# 04_Motor_Driver.net
KiCad netlist of a schematic drawn in Altium Designer
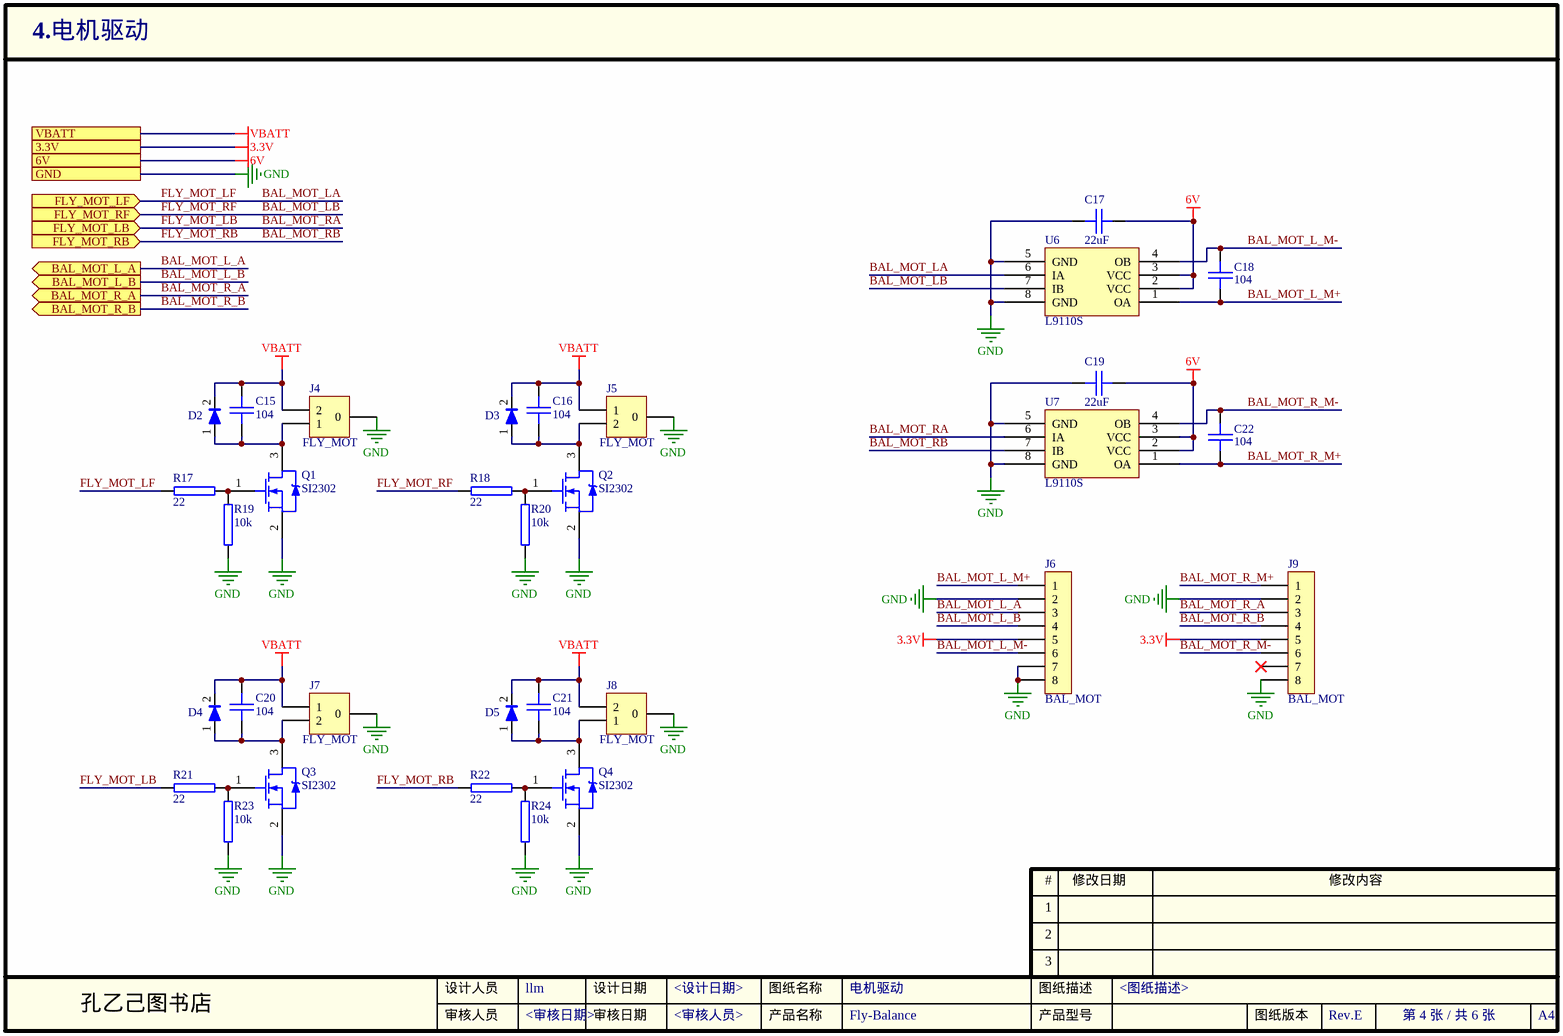
[diagram p0: 04_Motor_Driver.SchDoc]

(export (version "E")
  (design (tool "Eeschema 10.0.6"))
  (components
    (comp (ref "C15")
      (value "104")
      (footprint "0402C")
      (description "电容")
      (libsource (lib "MY_Schlib") (part "CAP"))
    )
    (comp (ref "C16")
      (value "104")
      (footprint "0402C")
      (description "电容")
      (libsource (lib "MY_Schlib") (part "CAP"))
    )
    (comp (ref "C17")
      (value "22uF")
      (footprint "0805C")
      (description "电容")
      (libsource (lib "MY_Schlib") (part "CAP"))
    )
    (comp (ref "C18")
      (value "104")
      (footprint "0402C")
      (description "电容")
      (libsource (lib "MY_Schlib") (part "CAP"))
    )
    (comp (ref "C19")
      (value "22uF")
      (footprint "0805C")
      (description "电容")
      (libsource (lib "MY_Schlib") (part "CAP"))
    )
    (comp (ref "C20")
      (value "104")
      (footprint "0402C")
      (description "电容")
      (libsource (lib "MY_Schlib") (part "CAP"))
    )
    (comp (ref "C21")
      (value "104")
      (footprint "0402C")
      (description "电容")
      (libsource (lib "MY_Schlib") (part "CAP"))
    )
    (comp (ref "C22")
      (value "104")
      (footprint "0402C")
      (description "电容")
      (libsource (lib "MY_Schlib") (part "CAP"))
    )
    (comp (ref "D2")
      (value "1N4001")
      (footprint "SOD-323")
      (description "二极管")
      (libsource (lib "MY_Schlib") (part "DIODE"))
    )
    (comp (ref "D3")
      (value "1N4001")
      (footprint "SOD-323")
      (description "二极管")
      (libsource (lib "MY_Schlib") (part "DIODE"))
    )
    (comp (ref "D4")
      (value "1N4001")
      (footprint "SOD-323")
      (description "二极管")
      (libsource (lib "MY_Schlib") (part "DIODE"))
    )
    (comp (ref "D5")
      (value "1N4001")
      (footprint "SOD-323")
      (description "二极管")
      (libsource (lib "MY_Schlib") (part "DIODE"))
    )
    (comp (ref "J4")
      (value "FLY_MOT")
      (footprint "CONN-SMD_2P-P1.25")
      (description "直流电机接口")
      (libsource (lib "Schlib") (part "CON"))
    )
    (comp (ref "J5")
      (value "FLY_MOT")
      (footprint "CONN-SMD_2P-P1.25")
      (description "直流电机接口")
      (libsource (lib "") (part "CON_1"))
    )
    (comp (ref "J6")
      (value "BAL_MOT")
      (footprint "CONN-SMD_6P-P2.00_DEALON_PH-6PWB")
      (description "Connector")
      (libsource (lib "MY_Schlib") (part "CON8"))
    )
    (comp (ref "J7")
      (value "FLY_MOT")
      (footprint "CONN-SMD_2P-P1.25")
      (description "直流电机接口")
      (libsource (lib "") (part "CON_1"))
    )
    (comp (ref "J8")
      (value "FLY_MOT")
      (footprint "CONN-SMD_2P-P1.25")
      (description "直流电机接口")
      (libsource (lib "Schlib") (part "CON"))
    )
    (comp (ref "J9")
      (value "BAL_MOT")
      (footprint "CONN-SMD_6P-P2.00_DEALON_PH-6PWB")
      (description "Connector")
      (libsource (lib "MY_Schlib") (part "CON8"))
    )
    (comp (ref "Q1")
      (value "SI2302")
      (footprint "SOT-23")
      (description "N-MOSFET")
      (libsource (lib "MY_Schlib") (part "N-MOS"))
    )
    (comp (ref "Q2")
      (value "SI2302")
      (footprint "SOT-23")
      (description "N-MOSFET")
      (libsource (lib "MY_Schlib") (part "N-MOS"))
    )
    (comp (ref "Q3")
      (value "SI2302")
      (footprint "SOT-23")
      (description "N-MOSFET")
      (libsource (lib "MY_Schlib") (part "N-MOS"))
    )
    (comp (ref "Q4")
      (value "SI2302")
      (footprint "SOT-23")
      (description "N-MOSFET")
      (libsource (lib "MY_Schlib") (part "N-MOS"))
    )
    (comp (ref "R17")
      (value "22")
      (footprint "0402R")
      (description "电阻")
      (libsource (lib "MY_Schlib") (part "RES"))
    )
    (comp (ref "R18")
      (value "22")
      (footprint "0402R")
      (description "电阻")
      (libsource (lib "MY_Schlib") (part "RES"))
    )
    (comp (ref "R19")
      (value "10k")
      (footprint "0402R")
      (description "电阻")
      (libsource (lib "MY_Schlib") (part "RES"))
    )
    (comp (ref "R20")
      (value "10k")
      (footprint "0402R")
      (description "电阻")
      (libsource (lib "MY_Schlib") (part "RES"))
    )
    (comp (ref "R21")
      (value "22")
      (footprint "0402R")
      (description "电阻")
      (libsource (lib "MY_Schlib") (part "RES"))
    )
    (comp (ref "R22")
      (value "22")
      (footprint "0402R")
      (description "电阻")
      (libsource (lib "MY_Schlib") (part "RES"))
    )
    (comp (ref "R23")
      (value "10k")
      (footprint "0402R")
      (description "电阻")
      (libsource (lib "MY_Schlib") (part "RES"))
    )
    (comp (ref "R24")
      (value "10k")
      (footprint "0402R")
      (description "电阻")
      (libsource (lib "MY_Schlib") (part "RES"))
    )
    (comp (ref "U6")
      (value "L9110S")
      (footprint "SOP-8_L4.9-W3.9-P1.27-LS6.0-BL")
      (description "H桥电机驱动芯片")
      (libsource (lib "MY_Schlib") (part "L9110S"))
    )
    (comp (ref "U7")
      (value "L9110S")
      (footprint "SOP-8_L4.9-W3.9-P1.27-LS6.0-BL")
      (description "H桥电机驱动芯片")
      (libsource (lib "MY_Schlib") (part "L9110S"))
    )
  )
  (nets
    (net (code "1") (name "/BAL_MOT_LA") (class "Default")
      (node (ref "R17") (pin "2") (pinfunction "2_2") (pintype "passive"))
      (node (ref "U6") (pin "6") (pinfunction "IA_6") (pintype "passive"))
    )
    (net (code "2") (name "/BAL_MOT_LB") (class "Default")
      (node (ref "R18") (pin "2") (pinfunction "2_2") (pintype "passive"))
      (node (ref "U6") (pin "7") (pinfunction "IB_7") (pintype "passive"))
    )
    (net (code "3") (name "/BAL_MOT_L_A") (class "Default")
      (node (ref "J6") (pin "3") (pinfunction "3_3") (pintype "passive"))
    )
    (net (code "4") (name "/BAL_MOT_L_B") (class "Default")
      (node (ref "J6") (pin "4") (pinfunction "4_4") (pintype "passive"))
    )
    (net (code "5") (name "/BAL_MOT_L_M+") (class "Default")
      (node (ref "C18") (pin "2") (pinfunction "2_2") (pintype "passive"))
      (node (ref "J6") (pin "1") (pinfunction "1_1") (pintype "passive"))
      (node (ref "U6") (pin "1") (pinfunction "OA_1") (pintype "passive"))
    )
    (net (code "6") (name "/BAL_MOT_L_M-") (class "Default")
      (node (ref "C18") (pin "1") (pinfunction "1_1") (pintype "passive"))
      (node (ref "J6") (pin "6") (pinfunction "6_6") (pintype "passive"))
      (node (ref "U6") (pin "4") (pinfunction "OB_4") (pintype "passive"))
    )
    (net (code "7") (name "/BAL_MOT_RA") (class "Default")
      (node (ref "R21") (pin "2") (pinfunction "2_2") (pintype "passive"))
      (node (ref "U7") (pin "6") (pinfunction "IA_6") (pintype "passive"))
    )
    (net (code "8") (name "/BAL_MOT_RB") (class "Default")
      (node (ref "R22") (pin "2") (pinfunction "2_2") (pintype "passive"))
      (node (ref "U7") (pin "7") (pinfunction "IB_7") (pintype "passive"))
    )
    (net (code "9") (name "/BAL_MOT_R_A") (class "Default")
      (node (ref "J9") (pin "3") (pinfunction "3_3") (pintype "passive"))
    )
    (net (code "10") (name "/BAL_MOT_R_B") (class "Default")
      (node (ref "J9") (pin "4") (pinfunction "4_4") (pintype "passive"))
    )
    (net (code "11") (name "/BAL_MOT_R_M+") (class "Default")
      (node (ref "C22") (pin "2") (pinfunction "2_2") (pintype "passive"))
      (node (ref "J9") (pin "1") (pinfunction "1_1") (pintype "passive"))
      (node (ref "U7") (pin "1") (pinfunction "OA_1") (pintype "passive"))
    )
    (net (code "12") (name "/BAL_MOT_R_M-") (class "Default")
      (node (ref "C22") (pin "1") (pinfunction "1_1") (pintype "passive"))
      (node (ref "J9") (pin "6") (pinfunction "6_6") (pintype "passive"))
      (node (ref "U7") (pin "4") (pinfunction "OB_4") (pintype "passive"))
    )
    (net (code "13") (name "3.3V") (class "Default")
      (node (ref "J6") (pin "5") (pinfunction "5_5") (pintype "passive"))
      (node (ref "J9") (pin "5") (pinfunction "5_5") (pintype "passive"))
    )
    (net (code "14") (name "6V") (class "Default")
      (node (ref "C17") (pin "1") (pinfunction "1_1") (pintype "passive"))
      (node (ref "C19") (pin "1") (pinfunction "1_1") (pintype "passive"))
      (node (ref "U6") (pin "2") (pinfunction "VCC_2") (pintype "passive"))
      (node (ref "U6") (pin "3") (pinfunction "VCC_3") (pintype "passive"))
      (node (ref "U7") (pin "2") (pinfunction "VCC_2") (pintype "passive"))
      (node (ref "U7") (pin "3") (pinfunction "VCC_3") (pintype "passive"))
    )
    (net (code "15") (name "GND") (class "Default")
      (node (ref "C17") (pin "2") (pinfunction "2_2") (pintype "passive"))
      (node (ref "C19") (pin "2") (pinfunction "2_2") (pintype "passive"))
      (node (ref "J4") (pin "0") (pinfunction "0_0") (pintype "passive"))
      (node (ref "J5") (pin "0") (pinfunction "0_0") (pintype "passive"))
      (node (ref "J6") (pin "2") (pinfunction "2_2") (pintype "passive"))
      (node (ref "J6") (pin "7") (pinfunction "7_7") (pintype "passive"))
      (node (ref "J6") (pin "8") (pinfunction "8_8") (pintype "passive"))
      (node (ref "J7") (pin "0") (pinfunction "0_0") (pintype "passive"))
      (node (ref "J8") (pin "0") (pinfunction "0_0") (pintype "passive"))
      (node (ref "J9") (pin "2") (pinfunction "2_2") (pintype "passive"))
      (node (ref "J9") (pin "8") (pinfunction "8_8") (pintype "passive"))
      (node (ref "Q1") (pin "2") (pinfunction "S_2") (pintype "passive"))
      (node (ref "Q2") (pin "2") (pinfunction "S_2") (pintype "passive"))
      (node (ref "Q3") (pin "2") (pinfunction "S_2") (pintype "passive"))
      (node (ref "Q4") (pin "2") (pinfunction "S_2") (pintype "passive"))
      (node (ref "R19") (pin "2") (pinfunction "2_2") (pintype "passive"))
      (node (ref "R20") (pin "2") (pinfunction "2_2") (pintype "passive"))
      (node (ref "R23") (pin "2") (pinfunction "2_2") (pintype "passive"))
      (node (ref "R24") (pin "2") (pinfunction "2_2") (pintype "passive"))
      (node (ref "U6") (pin "5") (pinfunction "GND_5") (pintype "passive"))
      (node (ref "U6") (pin "8") (pinfunction "GND_8") (pintype "passive"))
      (node (ref "U7") (pin "5") (pinfunction "GND_5") (pintype "passive"))
      (node (ref "U7") (pin "8") (pinfunction "GND_8") (pintype "passive"))
    )
    (net (code "16") (name "Net-(Q1-D)") (class "Default")
      (node (ref "C15") (pin "2") (pinfunction "2_2") (pintype "passive"))
      (node (ref "D2") (pin "1") (pinfunction "1_1") (pintype "passive"))
      (node (ref "J4") (pin "1") (pinfunction "1_1") (pintype "passive"))
      (node (ref "Q1") (pin "3") (pinfunction "D_3") (pintype "passive"))
    )
    (net (code "17") (name "Net-(Q1-G)") (class "Default")
      (node (ref "Q1") (pin "1") (pinfunction "G_1") (pintype "passive"))
      (node (ref "R17") (pin "1") (pinfunction "1_1") (pintype "passive"))
      (node (ref "R19") (pin "1") (pinfunction "1_1") (pintype "passive"))
    )
    (net (code "18") (name "Net-(Q2-D)") (class "Default")
      (node (ref "C16") (pin "2") (pinfunction "2_2") (pintype "passive"))
      (node (ref "D3") (pin "1") (pinfunction "1_1") (pintype "passive"))
      (node (ref "J5") (pin "2") (pinfunction "2_2") (pintype "passive"))
      (node (ref "Q2") (pin "3") (pinfunction "D_3") (pintype "passive"))
    )
    (net (code "19") (name "Net-(Q2-G)") (class "Default")
      (node (ref "Q2") (pin "1") (pinfunction "G_1") (pintype "passive"))
      (node (ref "R18") (pin "1") (pinfunction "1_1") (pintype "passive"))
      (node (ref "R20") (pin "1") (pinfunction "1_1") (pintype "passive"))
    )
    (net (code "20") (name "Net-(Q3-D)") (class "Default")
      (node (ref "C20") (pin "2") (pinfunction "2_2") (pintype "passive"))
      (node (ref "D4") (pin "1") (pinfunction "1_1") (pintype "passive"))
      (node (ref "J7") (pin "2") (pinfunction "2_2") (pintype "passive"))
      (node (ref "Q3") (pin "3") (pinfunction "D_3") (pintype "passive"))
    )
    (net (code "21") (name "Net-(Q3-G)") (class "Default")
      (node (ref "Q3") (pin "1") (pinfunction "G_1") (pintype "passive"))
      (node (ref "R21") (pin "1") (pinfunction "1_1") (pintype "passive"))
      (node (ref "R23") (pin "1") (pinfunction "1_1") (pintype "passive"))
    )
    (net (code "22") (name "Net-(Q4-D)") (class "Default")
      (node (ref "C21") (pin "2") (pinfunction "2_2") (pintype "passive"))
      (node (ref "D5") (pin "1") (pinfunction "1_1") (pintype "passive"))
      (node (ref "J8") (pin "1") (pinfunction "1_1") (pintype "passive"))
      (node (ref "Q4") (pin "3") (pinfunction "D_3") (pintype "passive"))
    )
    (net (code "23") (name "Net-(Q4-G)") (class "Default")
      (node (ref "Q4") (pin "1") (pinfunction "G_1") (pintype "passive"))
      (node (ref "R22") (pin "1") (pinfunction "1_1") (pintype "passive"))
      (node (ref "R24") (pin "1") (pinfunction "1_1") (pintype "passive"))
    )
    (net (code "24") (name "VBATT") (class "Default")
      (node (ref "C15") (pin "1") (pinfunction "1_1") (pintype "passive"))
      (node (ref "C16") (pin "1") (pinfunction "1_1") (pintype "passive"))
      (node (ref "C20") (pin "1") (pinfunction "1_1") (pintype "passive"))
      (node (ref "C21") (pin "1") (pinfunction "1_1") (pintype "passive"))
      (node (ref "D2") (pin "2") (pinfunction "2_2") (pintype "passive"))
      (node (ref "D3") (pin "2") (pinfunction "2_2") (pintype "passive"))
      (node (ref "D4") (pin "2") (pinfunction "2_2") (pintype "passive"))
      (node (ref "D5") (pin "2") (pinfunction "2_2") (pintype "passive"))
      (node (ref "J4") (pin "2") (pinfunction "2_2") (pintype "passive"))
      (node (ref "J5") (pin "1") (pinfunction "1_1") (pintype "passive"))
      (node (ref "J7") (pin "1") (pinfunction "1_1") (pintype "passive"))
      (node (ref "J8") (pin "2") (pinfunction "2_2") (pintype "passive"))
    )
    (net (code "25") (name "unconnected-(J9-Pad7)") (class "Default")
      (node (ref "J9") (pin "7") (pinfunction "7_7") (pintype "passive+no_connect"))
    )
  )
)
